# BCK_REVA_2.net
KiCad netlist of a schematic drawn in Altium Designer
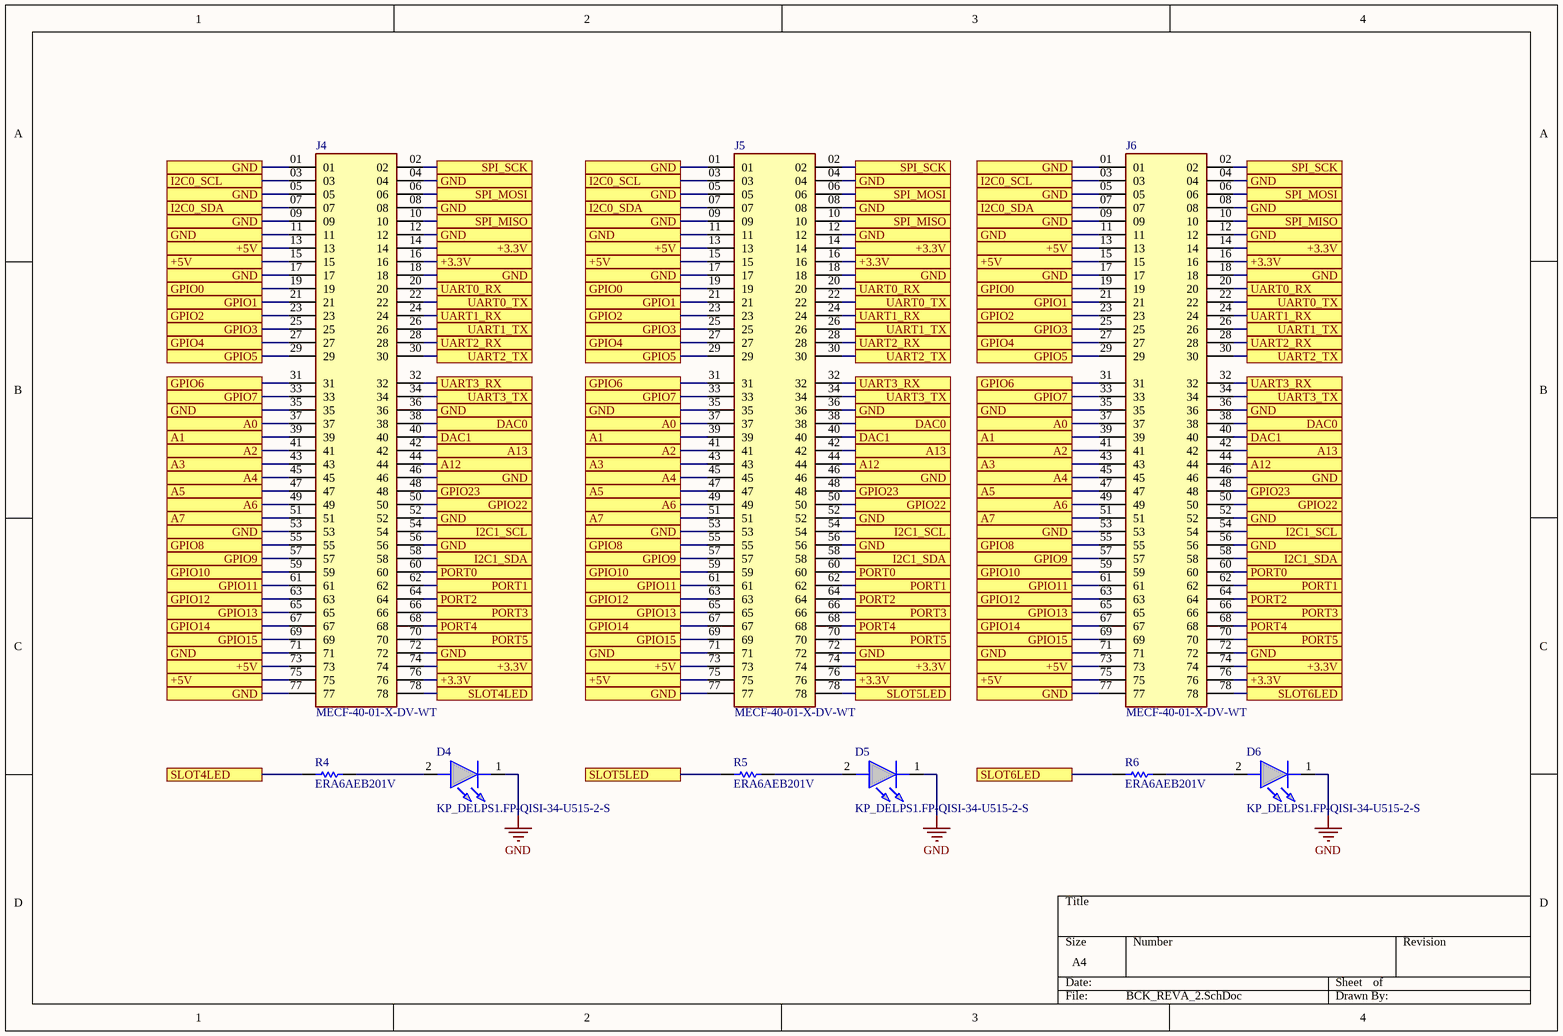
[diagram p0: BCK_REVA_2.SchDoc]

(export (version "E")
  (design (tool "Eeschema 10.0.6"))
  (components
    (comp (ref "D4")
      (value "KP_DELPS1.FP-QISI-34-U515-2-S")
      (footprint "KPDELPS1FPQISI34U5152S:KPDELPS1FPQISI34U5152S")
      (description "High Power LEDs - Single Color Pure Green TOPLED E1608")
      (fields
        (field (name "MANUFACTURER_PART_NUMBER") "KP DELPS1.FP-QISI-34-U515-2-S")
        (field (name "MOUSER PART NUMBER") "720-KPDELPS1FPA0817")
      )
      (libsource (lib "Backplane_REVA") (part "KP_DELPS1.FP-QISI-34-U515-2-S"))
    )
    (comp (ref "D5")
      (value "KP_DELPS1.FP-QISI-34-U515-2-S")
      (footprint "KPDELPS1FPQISI34U5152S:KPDELPS1FPQISI34U5152S")
      (description "High Power LEDs - Single Color Pure Green TOPLED E1608")
      (fields
        (field (name "MANUFACTURER_PART_NUMBER") "KP DELPS1.FP-QISI-34-U515-2-S")
        (field (name "MOUSER PART NUMBER") "720-KPDELPS1FPA0817")
      )
      (libsource (lib "Backplane_REVA") (part "KP_DELPS1.FP-QISI-34-U515-2-S"))
    )
    (comp (ref "D6")
      (value "KP_DELPS1.FP-QISI-34-U515-2-S")
      (footprint "KPDELPS1FPQISI34U5152S:KPDELPS1FPQISI34U5152S")
      (description "High Power LEDs - Single Color Pure Green TOPLED E1608")
      (fields
        (field (name "MANUFACTURER_PART_NUMBER") "KP DELPS1.FP-QISI-34-U515-2-S")
        (field (name "MOUSER PART NUMBER") "720-KPDELPS1FPA0817")
      )
      (libsource (lib "Backplane_REVA") (part "KP_DELPS1.FP-QISI-34-U515-2-S"))
    )
    (comp (ref "J4")
      (value "MECF-40-01-X-DV-WT")
      (footprint "SAMTEC_MECF-40-01-X-DV-WT:SAMTEC_MECF-40-01-X-DV-WT")
      (description "MECF .050\" EDGE CARD ASSEMBLY")
      (fields (field (name "MF") "Samtec"))
      (libsource (lib "Backplane_REVA") (part "MECF-40-01-X-DV-WT"))
    )
    (comp (ref "J5")
      (value "MECF-40-01-X-DV-WT")
      (footprint "SAMTEC_MECF-40-01-X-DV-WT:SAMTEC_MECF-40-01-X-DV-WT")
      (description "MECF .050\" EDGE CARD ASSEMBLY")
      (fields (field (name "MF") "Samtec"))
      (libsource (lib "Backplane_REVA") (part "MECF-40-01-X-DV-WT"))
    )
    (comp (ref "J6")
      (value "MECF-40-01-X-DV-WT")
      (footprint "SAMTEC_MECF-40-01-X-DV-WT:SAMTEC_MECF-40-01-X-DV-WT")
      (description "MECF .050\" EDGE CARD ASSEMBLY")
      (fields (field (name "MF") "Samtec"))
      (libsource (lib "Backplane_REVA") (part "MECF-40-01-X-DV-WT"))
    )
    (comp (ref "R4")
      (value "ERA6AEB201V")
      (footprint "RESC2013X60X40NL20T25")
      (fields (field (name "MANUFACTURER") "Panasonic"))
      (libsource (lib "Altium Content Vault") (part "RES"))
    )
    (comp (ref "R5")
      (value "ERA6AEB201V")
      (footprint "RESC2013X60X40NL20T25")
      (fields (field (name "MANUFACTURER") "Panasonic"))
      (libsource (lib "Altium Content Vault") (part "RES"))
    )
    (comp (ref "R6")
      (value "ERA6AEB201V")
      (footprint "RESC2013X60X40NL20T25")
      (fields (field (name "MANUFACTURER") "Panasonic"))
      (libsource (lib "Altium Content Vault") (part "RES"))
    )
  )
  (nets
    (net (code "1") (name "/+3.3V") (class "Default")
      (node (ref "J4") (pin "14") (pinfunction "14_14") (pintype "passive"))
      (node (ref "J4") (pin "16") (pinfunction "16_16") (pintype "passive"))
      (node (ref "J4") (pin "74") (pinfunction "74_74") (pintype "passive"))
      (node (ref "J4") (pin "76") (pinfunction "76_76") (pintype "passive"))
      (node (ref "J5") (pin "14") (pinfunction "14_14") (pintype "passive"))
      (node (ref "J5") (pin "16") (pinfunction "16_16") (pintype "passive"))
      (node (ref "J5") (pin "74") (pinfunction "74_74") (pintype "passive"))
      (node (ref "J5") (pin "76") (pinfunction "76_76") (pintype "passive"))
      (node (ref "J6") (pin "14") (pinfunction "14_14") (pintype "passive"))
      (node (ref "J6") (pin "16") (pinfunction "16_16") (pintype "passive"))
      (node (ref "J6") (pin "74") (pinfunction "74_74") (pintype "passive"))
      (node (ref "J6") (pin "76") (pinfunction "76_76") (pintype "passive"))
    )
    (net (code "2") (name "/+5V") (class "Default")
      (node (ref "J4") (pin "13") (pinfunction "13_13") (pintype "passive"))
      (node (ref "J4") (pin "15") (pinfunction "15_15") (pintype "passive"))
      (node (ref "J4") (pin "73") (pinfunction "73_73") (pintype "passive"))
      (node (ref "J4") (pin "75") (pinfunction "75_75") (pintype "passive"))
      (node (ref "J5") (pin "13") (pinfunction "13_13") (pintype "passive"))
      (node (ref "J5") (pin "15") (pinfunction "15_15") (pintype "passive"))
      (node (ref "J5") (pin "73") (pinfunction "73_73") (pintype "passive"))
      (node (ref "J5") (pin "75") (pinfunction "75_75") (pintype "passive"))
      (node (ref "J6") (pin "13") (pinfunction "13_13") (pintype "passive"))
      (node (ref "J6") (pin "15") (pinfunction "15_15") (pintype "passive"))
      (node (ref "J6") (pin "73") (pinfunction "73_73") (pintype "passive"))
      (node (ref "J6") (pin "75") (pinfunction "75_75") (pintype "passive"))
    )
    (net (code "3") (name "/A0") (class "Default")
      (node (ref "J4") (pin "37") (pinfunction "37_37") (pintype "passive"))
      (node (ref "J5") (pin "37") (pinfunction "37_37") (pintype "passive"))
      (node (ref "J6") (pin "37") (pinfunction "37_37") (pintype "passive"))
    )
    (net (code "4") (name "/A1") (class "Default")
      (node (ref "J4") (pin "39") (pinfunction "39_39") (pintype "passive"))
      (node (ref "J5") (pin "39") (pinfunction "39_39") (pintype "passive"))
      (node (ref "J6") (pin "39") (pinfunction "39_39") (pintype "passive"))
    )
    (net (code "5") (name "/A2") (class "Default")
      (node (ref "J4") (pin "41") (pinfunction "41_41") (pintype "passive"))
      (node (ref "J5") (pin "41") (pinfunction "41_41") (pintype "passive"))
      (node (ref "J6") (pin "41") (pinfunction "41_41") (pintype "passive"))
    )
    (net (code "6") (name "/A3") (class "Default")
      (node (ref "J4") (pin "43") (pinfunction "43_43") (pintype "passive"))
      (node (ref "J5") (pin "43") (pinfunction "43_43") (pintype "passive"))
      (node (ref "J6") (pin "43") (pinfunction "43_43") (pintype "passive"))
    )
    (net (code "7") (name "/A4") (class "Default")
      (node (ref "J4") (pin "45") (pinfunction "45_45") (pintype "passive"))
      (node (ref "J5") (pin "45") (pinfunction "45_45") (pintype "passive"))
      (node (ref "J6") (pin "45") (pinfunction "45_45") (pintype "passive"))
    )
    (net (code "8") (name "/A5") (class "Default")
      (node (ref "J4") (pin "47") (pinfunction "47_47") (pintype "passive"))
      (node (ref "J5") (pin "47") (pinfunction "47_47") (pintype "passive"))
      (node (ref "J6") (pin "47") (pinfunction "47_47") (pintype "passive"))
    )
    (net (code "9") (name "/A6") (class "Default")
      (node (ref "J4") (pin "49") (pinfunction "49_49") (pintype "passive"))
      (node (ref "J5") (pin "49") (pinfunction "49_49") (pintype "passive"))
      (node (ref "J6") (pin "49") (pinfunction "49_49") (pintype "passive"))
    )
    (net (code "10") (name "/A7") (class "Default")
      (node (ref "J4") (pin "51") (pinfunction "51_51") (pintype "passive"))
      (node (ref "J5") (pin "51") (pinfunction "51_51") (pintype "passive"))
      (node (ref "J6") (pin "51") (pinfunction "51_51") (pintype "passive"))
    )
    (net (code "11") (name "/A12") (class "Default")
      (node (ref "J4") (pin "44") (pinfunction "44_44") (pintype "passive"))
      (node (ref "J5") (pin "44") (pinfunction "44_44") (pintype "passive"))
      (node (ref "J6") (pin "44") (pinfunction "44_44") (pintype "passive"))
    )
    (net (code "12") (name "/A13") (class "Default")
      (node (ref "J4") (pin "42") (pinfunction "42_42") (pintype "passive"))
      (node (ref "J5") (pin "42") (pinfunction "42_42") (pintype "passive"))
      (node (ref "J6") (pin "42") (pinfunction "42_42") (pintype "passive"))
    )
    (net (code "13") (name "/DAC0") (class "Default")
      (node (ref "J4") (pin "38") (pinfunction "38_38") (pintype "passive"))
      (node (ref "J5") (pin "38") (pinfunction "38_38") (pintype "passive"))
      (node (ref "J6") (pin "38") (pinfunction "38_38") (pintype "passive"))
    )
    (net (code "14") (name "/DAC1") (class "Default")
      (node (ref "J4") (pin "40") (pinfunction "40_40") (pintype "passive"))
      (node (ref "J5") (pin "40") (pinfunction "40_40") (pintype "passive"))
      (node (ref "J6") (pin "40") (pinfunction "40_40") (pintype "passive"))
    )
    (net (code "15") (name "/GPIO0") (class "Default")
      (node (ref "J4") (pin "19") (pinfunction "19_19") (pintype "passive"))
      (node (ref "J5") (pin "19") (pinfunction "19_19") (pintype "passive"))
      (node (ref "J6") (pin "19") (pinfunction "19_19") (pintype "passive"))
    )
    (net (code "16") (name "/GPIO1") (class "Default")
      (node (ref "J4") (pin "21") (pinfunction "21_21") (pintype "passive"))
      (node (ref "J5") (pin "21") (pinfunction "21_21") (pintype "passive"))
      (node (ref "J6") (pin "21") (pinfunction "21_21") (pintype "passive"))
    )
    (net (code "17") (name "/GPIO2") (class "Default")
      (node (ref "J4") (pin "23") (pinfunction "23_23") (pintype "passive"))
      (node (ref "J5") (pin "23") (pinfunction "23_23") (pintype "passive"))
      (node (ref "J6") (pin "23") (pinfunction "23_23") (pintype "passive"))
    )
    (net (code "18") (name "/GPIO3") (class "Default")
      (node (ref "J4") (pin "25") (pinfunction "25_25") (pintype "passive"))
      (node (ref "J5") (pin "25") (pinfunction "25_25") (pintype "passive"))
      (node (ref "J6") (pin "25") (pinfunction "25_25") (pintype "passive"))
    )
    (net (code "19") (name "/GPIO4") (class "Default")
      (node (ref "J4") (pin "27") (pinfunction "27_27") (pintype "passive"))
      (node (ref "J5") (pin "27") (pinfunction "27_27") (pintype "passive"))
      (node (ref "J6") (pin "27") (pinfunction "27_27") (pintype "passive"))
    )
    (net (code "20") (name "/GPIO5") (class "Default")
      (node (ref "J4") (pin "29") (pinfunction "29_29") (pintype "passive"))
      (node (ref "J5") (pin "29") (pinfunction "29_29") (pintype "passive"))
      (node (ref "J6") (pin "29") (pinfunction "29_29") (pintype "passive"))
    )
    (net (code "21") (name "/GPIO6") (class "Default")
      (node (ref "J4") (pin "31") (pinfunction "31_31") (pintype "passive"))
      (node (ref "J5") (pin "31") (pinfunction "31_31") (pintype "passive"))
      (node (ref "J6") (pin "31") (pinfunction "31_31") (pintype "passive"))
    )
    (net (code "22") (name "/GPIO7") (class "Default")
      (node (ref "J4") (pin "33") (pinfunction "33_33") (pintype "passive"))
      (node (ref "J5") (pin "33") (pinfunction "33_33") (pintype "passive"))
      (node (ref "J6") (pin "33") (pinfunction "33_33") (pintype "passive"))
    )
    (net (code "23") (name "/GPIO8") (class "Default")
      (node (ref "J4") (pin "55") (pinfunction "55_55") (pintype "passive"))
      (node (ref "J5") (pin "55") (pinfunction "55_55") (pintype "passive"))
      (node (ref "J6") (pin "55") (pinfunction "55_55") (pintype "passive"))
    )
    (net (code "24") (name "/GPIO9") (class "Default")
      (node (ref "J4") (pin "57") (pinfunction "57_57") (pintype "passive"))
      (node (ref "J5") (pin "57") (pinfunction "57_57") (pintype "passive"))
      (node (ref "J6") (pin "57") (pinfunction "57_57") (pintype "passive"))
    )
    (net (code "25") (name "/GPIO10") (class "Default")
      (node (ref "J4") (pin "59") (pinfunction "59_59") (pintype "passive"))
      (node (ref "J5") (pin "59") (pinfunction "59_59") (pintype "passive"))
      (node (ref "J6") (pin "59") (pinfunction "59_59") (pintype "passive"))
    )
    (net (code "26") (name "/GPIO11") (class "Default")
      (node (ref "J4") (pin "61") (pinfunction "61_61") (pintype "passive"))
      (node (ref "J5") (pin "61") (pinfunction "61_61") (pintype "passive"))
      (node (ref "J6") (pin "61") (pinfunction "61_61") (pintype "passive"))
    )
    (net (code "27") (name "/GPIO12") (class "Default")
      (node (ref "J4") (pin "63") (pinfunction "63_63") (pintype "passive"))
      (node (ref "J5") (pin "63") (pinfunction "63_63") (pintype "passive"))
      (node (ref "J6") (pin "63") (pinfunction "63_63") (pintype "passive"))
    )
    (net (code "28") (name "/GPIO13") (class "Default")
      (node (ref "J4") (pin "65") (pinfunction "65_65") (pintype "passive"))
      (node (ref "J5") (pin "65") (pinfunction "65_65") (pintype "passive"))
      (node (ref "J6") (pin "65") (pinfunction "65_65") (pintype "passive"))
    )
    (net (code "29") (name "/GPIO14") (class "Default")
      (node (ref "J4") (pin "67") (pinfunction "67_67") (pintype "passive"))
      (node (ref "J5") (pin "67") (pinfunction "67_67") (pintype "passive"))
      (node (ref "J6") (pin "67") (pinfunction "67_67") (pintype "passive"))
    )
    (net (code "30") (name "/GPIO15") (class "Default")
      (node (ref "J4") (pin "69") (pinfunction "69_69") (pintype "passive"))
      (node (ref "J5") (pin "69") (pinfunction "69_69") (pintype "passive"))
      (node (ref "J6") (pin "69") (pinfunction "69_69") (pintype "passive"))
    )
    (net (code "31") (name "/GPIO22") (class "Default")
      (node (ref "J4") (pin "50") (pinfunction "50_50") (pintype "passive"))
      (node (ref "J5") (pin "50") (pinfunction "50_50") (pintype "passive"))
      (node (ref "J6") (pin "50") (pinfunction "50_50") (pintype "passive"))
    )
    (net (code "32") (name "/GPIO23") (class "Default")
      (node (ref "J4") (pin "48") (pinfunction "48_48") (pintype "passive"))
      (node (ref "J5") (pin "48") (pinfunction "48_48") (pintype "passive"))
      (node (ref "J6") (pin "48") (pinfunction "48_48") (pintype "passive"))
    )
    (net (code "33") (name "/I2C0_SCL") (class "Default")
      (node (ref "J4") (pin "03") (pinfunction "03_03") (pintype "passive"))
      (node (ref "J5") (pin "03") (pinfunction "03_03") (pintype "passive"))
      (node (ref "J6") (pin "03") (pinfunction "03_03") (pintype "passive"))
    )
    (net (code "34") (name "/I2C0_SDA") (class "Default")
      (node (ref "J4") (pin "07") (pinfunction "07_07") (pintype "passive"))
      (node (ref "J5") (pin "07") (pinfunction "07_07") (pintype "passive"))
      (node (ref "J6") (pin "07") (pinfunction "07_07") (pintype "passive"))
    )
    (net (code "35") (name "/I2C1_SCL") (class "Default")
      (node (ref "J4") (pin "54") (pinfunction "54_54") (pintype "passive"))
      (node (ref "J5") (pin "54") (pinfunction "54_54") (pintype "passive"))
      (node (ref "J6") (pin "54") (pinfunction "54_54") (pintype "passive"))
    )
    (net (code "36") (name "/I2C1_SDA") (class "Default")
      (node (ref "J4") (pin "58") (pinfunction "58_58") (pintype "passive"))
      (node (ref "J5") (pin "58") (pinfunction "58_58") (pintype "passive"))
      (node (ref "J6") (pin "58") (pinfunction "58_58") (pintype "passive"))
    )
    (net (code "37") (name "/PORT0") (class "Default")
      (node (ref "J4") (pin "60") (pinfunction "60_60") (pintype "passive"))
      (node (ref "J5") (pin "60") (pinfunction "60_60") (pintype "passive"))
      (node (ref "J6") (pin "60") (pinfunction "60_60") (pintype "passive"))
    )
    (net (code "38") (name "/PORT1") (class "Default")
      (node (ref "J4") (pin "62") (pinfunction "62_62") (pintype "passive"))
      (node (ref "J5") (pin "62") (pinfunction "62_62") (pintype "passive"))
      (node (ref "J6") (pin "62") (pinfunction "62_62") (pintype "passive"))
    )
    (net (code "39") (name "/PORT2") (class "Default")
      (node (ref "J4") (pin "64") (pinfunction "64_64") (pintype "passive"))
      (node (ref "J5") (pin "64") (pinfunction "64_64") (pintype "passive"))
      (node (ref "J6") (pin "64") (pinfunction "64_64") (pintype "passive"))
    )
    (net (code "40") (name "/PORT3") (class "Default")
      (node (ref "J4") (pin "66") (pinfunction "66_66") (pintype "passive"))
      (node (ref "J5") (pin "66") (pinfunction "66_66") (pintype "passive"))
      (node (ref "J6") (pin "66") (pinfunction "66_66") (pintype "passive"))
    )
    (net (code "41") (name "/PORT4") (class "Default")
      (node (ref "J4") (pin "68") (pinfunction "68_68") (pintype "passive"))
      (node (ref "J5") (pin "68") (pinfunction "68_68") (pintype "passive"))
      (node (ref "J6") (pin "68") (pinfunction "68_68") (pintype "passive"))
    )
    (net (code "42") (name "/PORT5") (class "Default")
      (node (ref "J4") (pin "70") (pinfunction "70_70") (pintype "passive"))
      (node (ref "J5") (pin "70") (pinfunction "70_70") (pintype "passive"))
      (node (ref "J6") (pin "70") (pinfunction "70_70") (pintype "passive"))
    )
    (net (code "43") (name "/SLOT4LED") (class "Default")
      (node (ref "J4") (pin "78") (pinfunction "78_78") (pintype "passive"))
      (node (ref "R4") (pin "1") (pinfunction "1_1") (pintype "passive"))
    )
    (net (code "44") (name "/SLOT5LED") (class "Default")
      (node (ref "J5") (pin "78") (pinfunction "78_78") (pintype "passive"))
      (node (ref "R5") (pin "1") (pinfunction "1_1") (pintype "passive"))
    )
    (net (code "45") (name "/SLOT6LED") (class "Default")
      (node (ref "J6") (pin "78") (pinfunction "78_78") (pintype "passive"))
      (node (ref "R6") (pin "1") (pinfunction "1_1") (pintype "passive"))
    )
    (net (code "46") (name "/SPI_MISO") (class "Default")
      (node (ref "J4") (pin "10") (pinfunction "10_10") (pintype "passive"))
      (node (ref "J5") (pin "10") (pinfunction "10_10") (pintype "passive"))
      (node (ref "J6") (pin "10") (pinfunction "10_10") (pintype "passive"))
    )
    (net (code "47") (name "/SPI_MOSI") (class "Default")
      (node (ref "J4") (pin "06") (pinfunction "06_06") (pintype "passive"))
      (node (ref "J5") (pin "06") (pinfunction "06_06") (pintype "passive"))
      (node (ref "J6") (pin "06") (pinfunction "06_06") (pintype "passive"))
    )
    (net (code "48") (name "/SPI_SCK") (class "Default")
      (node (ref "J4") (pin "02") (pinfunction "02_02") (pintype "passive"))
      (node (ref "J5") (pin "02") (pinfunction "02_02") (pintype "passive"))
      (node (ref "J6") (pin "02") (pinfunction "02_02") (pintype "passive"))
    )
    (net (code "49") (name "/UART0_RX") (class "Default")
      (node (ref "J4") (pin "20") (pinfunction "20_20") (pintype "passive"))
      (node (ref "J5") (pin "20") (pinfunction "20_20") (pintype "passive"))
      (node (ref "J6") (pin "20") (pinfunction "20_20") (pintype "passive"))
    )
    (net (code "50") (name "/UART0_TX") (class "Default")
      (node (ref "J4") (pin "22") (pinfunction "22_22") (pintype "passive"))
      (node (ref "J5") (pin "22") (pinfunction "22_22") (pintype "passive"))
      (node (ref "J6") (pin "22") (pinfunction "22_22") (pintype "passive"))
    )
    (net (code "51") (name "/UART1_RX") (class "Default")
      (node (ref "J4") (pin "24") (pinfunction "24_24") (pintype "passive"))
      (node (ref "J5") (pin "24") (pinfunction "24_24") (pintype "passive"))
      (node (ref "J6") (pin "24") (pinfunction "24_24") (pintype "passive"))
    )
    (net (code "52") (name "/UART1_TX") (class "Default")
      (node (ref "J4") (pin "26") (pinfunction "26_26") (pintype "passive"))
      (node (ref "J5") (pin "26") (pinfunction "26_26") (pintype "passive"))
      (node (ref "J6") (pin "26") (pinfunction "26_26") (pintype "passive"))
    )
    (net (code "53") (name "/UART2_RX") (class "Default")
      (node (ref "J4") (pin "28") (pinfunction "28_28") (pintype "passive"))
      (node (ref "J5") (pin "28") (pinfunction "28_28") (pintype "passive"))
      (node (ref "J6") (pin "28") (pinfunction "28_28") (pintype "passive"))
    )
    (net (code "54") (name "/UART2_TX") (class "Default")
      (node (ref "J4") (pin "30") (pinfunction "30_30") (pintype "passive"))
      (node (ref "J5") (pin "30") (pinfunction "30_30") (pintype "passive"))
      (node (ref "J6") (pin "30") (pinfunction "30_30") (pintype "passive"))
    )
    (net (code "55") (name "/UART3_RX") (class "Default")
      (node (ref "J4") (pin "32") (pinfunction "32_32") (pintype "passive"))
      (node (ref "J5") (pin "32") (pinfunction "32_32") (pintype "passive"))
      (node (ref "J6") (pin "32") (pinfunction "32_32") (pintype "passive"))
    )
    (net (code "56") (name "/UART3_TX") (class "Default")
      (node (ref "J4") (pin "34") (pinfunction "34_34") (pintype "passive"))
      (node (ref "J5") (pin "34") (pinfunction "34_34") (pintype "passive"))
      (node (ref "J6") (pin "34") (pinfunction "34_34") (pintype "passive"))
    )
    (net (code "57") (name "GND") (class "Default")
      (node (ref "D4") (pin "1") (pinfunction "K_1") (pintype "passive"))
      (node (ref "D5") (pin "1") (pinfunction "K_1") (pintype "passive"))
      (node (ref "D6") (pin "1") (pinfunction "K_1") (pintype "passive"))
      (node (ref "J4") (pin "01") (pinfunction "01_01") (pintype "passive"))
      (node (ref "J4") (pin "04") (pinfunction "04_04") (pintype "passive"))
      (node (ref "J4") (pin "05") (pinfunction "05_05") (pintype "passive"))
      (node (ref "J4") (pin "08") (pinfunction "08_08") (pintype "passive"))
      (node (ref "J4") (pin "09") (pinfunction "09_09") (pintype "passive"))
      (node (ref "J4") (pin "11") (pinfunction "11_11") (pintype "passive"))
      (node (ref "J4") (pin "12") (pinfunction "12_12") (pintype "passive"))
      (node (ref "J4") (pin "17") (pinfunction "17_17") (pintype "passive"))
      (node (ref "J4") (pin "18") (pinfunction "18_18") (pintype "passive"))
      (node (ref "J4") (pin "35") (pinfunction "35_35") (pintype "passive"))
      (node (ref "J4") (pin "36") (pinfunction "36_36") (pintype "passive"))
      (node (ref "J4") (pin "46") (pinfunction "46_46") (pintype "passive"))
      (node (ref "J4") (pin "52") (pinfunction "52_52") (pintype "passive"))
      (node (ref "J4") (pin "53") (pinfunction "53_53") (pintype "passive"))
      (node (ref "J4") (pin "56") (pinfunction "56_56") (pintype "passive"))
      (node (ref "J4") (pin "71") (pinfunction "71_71") (pintype "passive"))
      (node (ref "J4") (pin "72") (pinfunction "72_72") (pintype "passive"))
      (node (ref "J4") (pin "77") (pinfunction "77_77") (pintype "passive"))
      (node (ref "J5") (pin "01") (pinfunction "01_01") (pintype "passive"))
      (node (ref "J5") (pin "04") (pinfunction "04_04") (pintype "passive"))
      (node (ref "J5") (pin "05") (pinfunction "05_05") (pintype "passive"))
      (node (ref "J5") (pin "08") (pinfunction "08_08") (pintype "passive"))
      (node (ref "J5") (pin "09") (pinfunction "09_09") (pintype "passive"))
      (node (ref "J5") (pin "11") (pinfunction "11_11") (pintype "passive"))
      (node (ref "J5") (pin "12") (pinfunction "12_12") (pintype "passive"))
      (node (ref "J5") (pin "17") (pinfunction "17_17") (pintype "passive"))
      (node (ref "J5") (pin "18") (pinfunction "18_18") (pintype "passive"))
      (node (ref "J5") (pin "35") (pinfunction "35_35") (pintype "passive"))
      (node (ref "J5") (pin "36") (pinfunction "36_36") (pintype "passive"))
      (node (ref "J5") (pin "46") (pinfunction "46_46") (pintype "passive"))
      (node (ref "J5") (pin "52") (pinfunction "52_52") (pintype "passive"))
      (node (ref "J5") (pin "53") (pinfunction "53_53") (pintype "passive"))
      (node (ref "J5") (pin "56") (pinfunction "56_56") (pintype "passive"))
      (node (ref "J5") (pin "71") (pinfunction "71_71") (pintype "passive"))
      (node (ref "J5") (pin "72") (pinfunction "72_72") (pintype "passive"))
      (node (ref "J5") (pin "77") (pinfunction "77_77") (pintype "passive"))
      (node (ref "J6") (pin "01") (pinfunction "01_01") (pintype "passive"))
      (node (ref "J6") (pin "04") (pinfunction "04_04") (pintype "passive"))
      (node (ref "J6") (pin "05") (pinfunction "05_05") (pintype "passive"))
      (node (ref "J6") (pin "08") (pinfunction "08_08") (pintype "passive"))
      (node (ref "J6") (pin "09") (pinfunction "09_09") (pintype "passive"))
      (node (ref "J6") (pin "11") (pinfunction "11_11") (pintype "passive"))
      (node (ref "J6") (pin "12") (pinfunction "12_12") (pintype "passive"))
      (node (ref "J6") (pin "17") (pinfunction "17_17") (pintype "passive"))
      (node (ref "J6") (pin "18") (pinfunction "18_18") (pintype "passive"))
      (node (ref "J6") (pin "35") (pinfunction "35_35") (pintype "passive"))
      (node (ref "J6") (pin "36") (pinfunction "36_36") (pintype "passive"))
      (node (ref "J6") (pin "46") (pinfunction "46_46") (pintype "passive"))
      (node (ref "J6") (pin "52") (pinfunction "52_52") (pintype "passive"))
      (node (ref "J6") (pin "53") (pinfunction "53_53") (pintype "passive"))
      (node (ref "J6") (pin "56") (pinfunction "56_56") (pintype "passive"))
      (node (ref "J6") (pin "71") (pinfunction "71_71") (pintype "passive"))
      (node (ref "J6") (pin "72") (pinfunction "72_72") (pintype "passive"))
      (node (ref "J6") (pin "77") (pinfunction "77_77") (pintype "passive"))
    )
    (net (code "58") (name "Net-(D4-A)") (class "Default")
      (node (ref "D4") (pin "2") (pinfunction "A_2") (pintype "passive"))
      (node (ref "R4") (pin "2") (pinfunction "2_2") (pintype "passive"))
    )
    (net (code "59") (name "Net-(D5-A)") (class "Default")
      (node (ref "D5") (pin "2") (pinfunction "A_2") (pintype "passive"))
      (node (ref "R5") (pin "2") (pinfunction "2_2") (pintype "passive"))
    )
    (net (code "60") (name "Net-(D6-A)") (class "Default")
      (node (ref "D6") (pin "2") (pinfunction "A_2") (pintype "passive"))
      (node (ref "R6") (pin "2") (pinfunction "2_2") (pintype "passive"))
    )
  )
)
